# Voltage_Regulation.net
KiCad netlist of a schematic drawn in Altium Designer
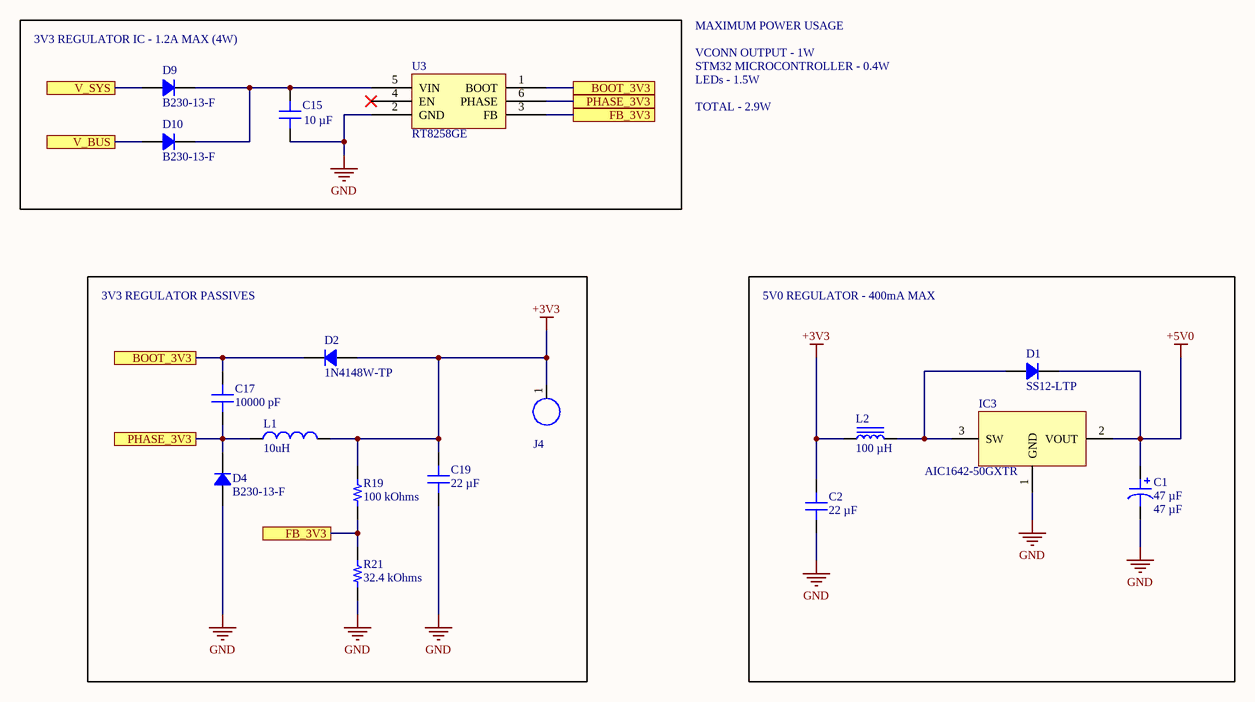
[diagram p0: Voltage_Regulation.SchDoc]

(export (version "E")
  (design (tool "Eeschema 10.0.6"))
  (components
    (comp (ref "C1")
      (value "47 µF")
      (footprint "CAP POL 1411_3528")
      (description "CAP TANT 47UF 10% 10V 1411")
      (fields
        (field (name "PART NUMBER") "T494B476K010AT")
        (field (name "ALTIUM_VALUE") "47 µF")
        (field (name "MANUFACTURER") "KEMET")
      )
      (libsource (lib "Celestial Altium Library - altium_library") (part "Polarised Capacitor"))
    )
    (comp (ref "C2")
      (value "22 µF")
      (footprint "CAP 1206_3216 - 0.8MM")
      (description "CAP CER 22UF 6.3V X7R 1206")
      (fields
        (field (name "PART NUMBER") "GCM31CR70J226KE23L")
        (field (name "MANUFACTURER") "Murata Electronics")
      )
      (libsource (lib "Celestial Altium Library - altium_library") (part "Capacitor"))
    )
    (comp (ref "C15")
      (value "10 µF")
      (footprint "CAP 1206_3216 - 0.8MM")
      (description "CAP CER 10UF 25V X7R 1206")
      (fields
        (field (name "PART NUMBER") "GRM31CR71E106MA12K")
        (field (name "MANUFACTURER") "Murata Electronics")
      )
      (libsource (lib "Celestial Altium Library - altium_library") (part "Capacitor"))
    )
    (comp (ref "C17")
      (value "10000 pF")
      (footprint "CAP 0402_1005")
      (description "CAP CER 10000PF 10V X7R 0402")
      (fields
        (field (name "PART NUMBER") "VJ0402Y103JXQCW1BC")
        (field (name "MANUFACTURER") "Vishay Vitramon")
      )
      (libsource (lib "Celestial Altium Library - altium_library") (part "Capacitor"))
    )
    (comp (ref "C19")
      (value "22 µF")
      (footprint "CAP 1206_3216 - 0.8MM")
      (description "CAP CER 22UF 6.3V X7R 1206")
      (fields
        (field (name "PART NUMBER") "GCM31CR70J226KE23L")
        (field (name "MANUFACTURER") "Murata Electronics")
      )
      (libsource (lib "Celestial Altium Library - altium_library") (part "Capacitor"))
    )
    (comp (ref "D1")
      (value "SS12-LTP")
      (footprint "DO214AC SMA")
      (description "DIODE SCHOTTKY 20V 1A DO214AC")
      (fields (field (name "MANUFACTURER") "Micro Commercial Co"))
      (libsource (lib "Celestial Altium Library - altium_library") (part "Diode"))
    )
    (comp (ref "D2")
      (value "1N4148W-TP")
      (footprint "SOD-123")
      (description "DIODE GEN PURP 100V 150MA SOD123")
      (fields (field (name "MANUFACTURER") "Micro Commercial Co"))
      (libsource (lib "Celestial Altium Library - altium_library") (part "Diode"))
    )
    (comp (ref "D4")
      (value "B230-13-F")
      (footprint "DO214AA SMB")
      (description "DIODE SCHOTTKY 30V 2A SMB")
      (fields (field (name "MANUFACTURER") "Diodes Incorporated"))
      (libsource (lib "Celestial Altium Library - altium_library") (part "Diode"))
    )
    (comp (ref "D9")
      (value "B230-13-F")
      (footprint "DO214AA SMB")
      (description "DIODE SCHOTTKY 30V 2A SMB")
      (fields (field (name "MANUFACTURER") "Diodes Incorporated"))
      (libsource (lib "Celestial Altium Library - altium_library") (part "Diode"))
    )
    (comp (ref "D10")
      (value "B230-13-F")
      (footprint "DO214AA SMB")
      (description "DIODE SCHOTTKY 30V 2A SMB")
      (fields (field (name "MANUFACTURER") "Diodes Incorporated"))
      (libsource (lib "Celestial Altium Library - altium_library") (part "Diode"))
    )
    (comp (ref "IC3")
      (value "AIC1642-50GXTR")
      (footprint "SOT89-150P410X160-3N")
      (description "C238214 NO Boost type 1 Boost 5V 0.9V~1.5V 400mA 100kHz SOT-89(SOT-89-3) DC-DC Converters ROHS")
      (libsource (lib "Schlib2") (part "AIC1642-50GXTR"))
    )
    (comp (ref "J4")
      (value "Large Board Solder Point")
      (footprint "Large Solder Point")
      (libsource (lib "Schlib2") (part "Large Board Solder Point"))
    )
    (comp (ref "L1")
      (value "10uH")
      (footprint "0630CDMCCDS-100MC")
      (description "4A 10uH ±20% 67mΩ SMD,7x6.6x2.8mm Power Inductors ROHS")
      (libsource (lib "Schlib2") (part "0630CDMCCDS-100MC"))
    )
    (comp (ref "L2")
      (value "100 µH")
      (footprint "LAIRD TYS5040")
      (description "FIXED IND 100UH 700MA 560MOHM SM")
      (fields
        (field (name "PART NUMBER") "TYS5040101M-10")
        (field (name "MANUFACTURER") "Laird-Signal Integrity Products")
      )
      (libsource (lib "Celestial Altium Library - altium_library") (part "Inductor"))
    )
    (comp (ref "R19")
      (value "100 kOhms")
      (footprint "RES 0402_1005")
      (description "RES 100K OHM 0.1% 1/10W 0402")
      (fields
        (field (name "PART NUMBER") "RP73PF1E100KBTD")
        (field (name "MANUFACTURER") "TE Connectivity Passive Product")
      )
      (libsource (lib "Celestial Altium Library - altium_library") (part "Resistor"))
    )
    (comp (ref "R21")
      (value "32.4 kOhms")
      (footprint "RES 0402_1005")
      (description "RES SMD 32.4KOHM 0.1% 1/16W 0402")
      (fields
        (field (name "PART NUMBER") "CPF0402B32K4E1")
        (field (name "MANUFACTURER") "TE Connectivity Passive Product")
      )
      (libsource (lib "Celestial Altium Library - altium_library") (part "Resistor"))
    )
    (comp (ref "U3")
      (value "RT8258GE")
      (footprint "SOT100P279X130-6N")
      (description "RICHTEK 1.2A, 24V, 700kHz Step-Down Converter SOT23-6")
      (libsource (lib "Schlib2") (part "RT8258GE"))
    )
  )
  (nets
    (net (code "1") (name "+3V3") (class "Default")
      (node (ref "C19") (pin "1") (pinfunction "1_1") (pintype "passive"))
      (node (ref "C2") (pin "1") (pinfunction "1_1") (pintype "passive"))
      (node (ref "D2") (pin "1") (pinfunction "1_1") (pintype "passive"))
      (node (ref "J4") (pin "1") (pintype "passive"))
      (node (ref "L1") (pin "2") (pinfunction "2_2") (pintype "passive"))
      (node (ref "L2") (pin "1") (pinfunction "1_1") (pintype "passive"))
      (node (ref "R19") (pin "2") (pinfunction "2_2") (pintype "passive"))
    )
    (net (code "2") (name "+5V0") (class "Default")
      (node (ref "C1") (pin "1") (pinfunction "1_1") (pintype "passive"))
      (node (ref "D1") (pin "2") (pinfunction "2_2") (pintype "passive"))
      (node (ref "IC3") (pin "2") (pinfunction "VOUT_2") (pintype "passive"))
    )
    (net (code "3") (name "/BOOT_3V3") (class "Default")
      (node (ref "C17") (pin "2") (pinfunction "2_2") (pintype "passive"))
      (node (ref "D2") (pin "2") (pinfunction "2_2") (pintype "passive"))
      (node (ref "U3") (pin "1") (pinfunction "BOOT_1") (pintype "passive"))
    )
    (net (code "4") (name "/FB_3V3") (class "Default")
      (node (ref "R19") (pin "1") (pinfunction "1_1") (pintype "passive"))
      (node (ref "R21") (pin "2") (pinfunction "2_2") (pintype "passive"))
      (node (ref "U3") (pin "3") (pinfunction "FB_3") (pintype "passive"))
    )
    (net (code "5") (name "/PHASE_3V3") (class "Default")
      (node (ref "C17") (pin "1") (pinfunction "1_1") (pintype "passive"))
      (node (ref "D4") (pin "2") (pinfunction "2_2") (pintype "passive"))
      (node (ref "L1") (pin "1") (pinfunction "1_1") (pintype "passive"))
      (node (ref "U3") (pin "6") (pinfunction "PHASE_6") (pintype "passive"))
    )
    (net (code "6") (name "/V_BUS") (class "Default")
      (node (ref "D10") (pin "1") (pinfunction "1_1") (pintype "passive"))
    )
    (net (code "7") (name "/V_SYS") (class "Default")
      (node (ref "D9") (pin "1") (pinfunction "1_1") (pintype "passive"))
    )
    (net (code "8") (name "GND") (class "Default")
      (node (ref "C1") (pin "2") (pinfunction "2_2") (pintype "passive"))
      (node (ref "C15") (pin "1") (pinfunction "1_1") (pintype "passive"))
      (node (ref "C19") (pin "2") (pinfunction "2_2") (pintype "passive"))
      (node (ref "C2") (pin "2") (pinfunction "2_2") (pintype "passive"))
      (node (ref "D4") (pin "1") (pinfunction "1_1") (pintype "passive"))
      (node (ref "IC3") (pin "1") (pinfunction "GND_1") (pintype "passive"))
      (node (ref "R21") (pin "1") (pinfunction "1_1") (pintype "passive"))
      (node (ref "U3") (pin "2") (pinfunction "GND_2") (pintype "passive"))
    )
    (net (code "9") (name "Net-(IC3-SW)") (class "Default")
      (node (ref "D1") (pin "1") (pinfunction "1_1") (pintype "passive"))
      (node (ref "IC3") (pin "3") (pinfunction "SW_3") (pintype "passive"))
      (node (ref "L2") (pin "2") (pinfunction "2_2") (pintype "passive"))
    )
    (net (code "10") (name "Net-(U3-VIN)") (class "Default")
      (node (ref "C15") (pin "2") (pinfunction "2_2") (pintype "passive"))
      (node (ref "D10") (pin "2") (pinfunction "2_2") (pintype "passive"))
      (node (ref "D9") (pin "2") (pinfunction "2_2") (pintype "passive"))
      (node (ref "U3") (pin "5") (pinfunction "VIN_5") (pintype "passive"))
    )
    (net (code "11") (name "unconnected-(U3-EN-Pad4)") (class "Default")
      (node (ref "U3") (pin "4") (pinfunction "EN_4") (pintype "passive+no_connect"))
    )
  )
)
